# tda2009.net
KiCad netlist of a schematic drawn in EAGLE
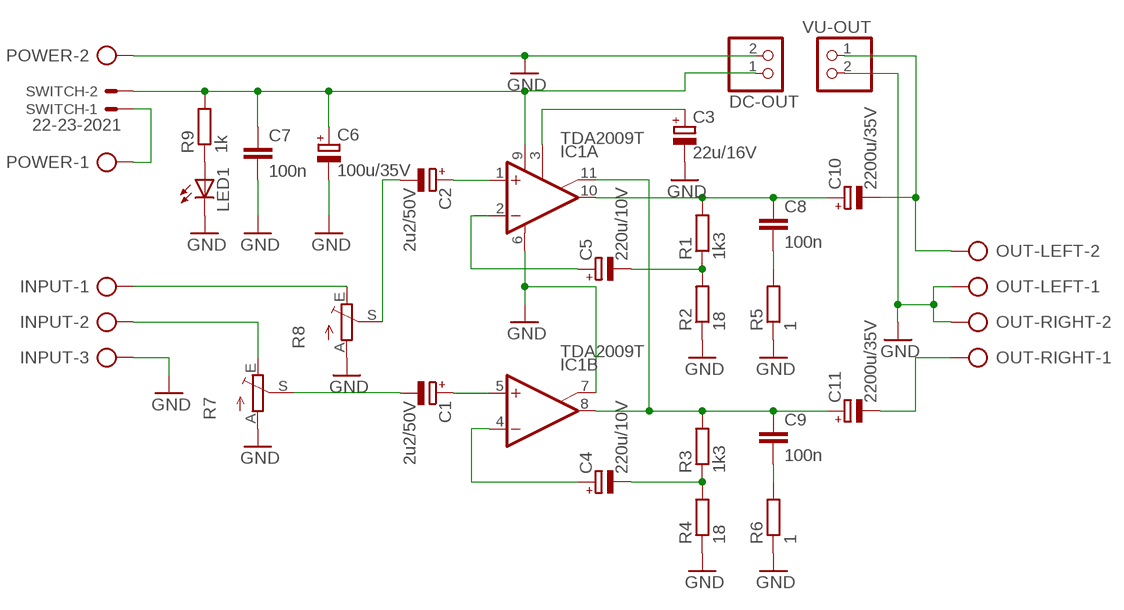
[diagram p0: schematic, sheet 1]

(export (version "E")
  (design (tool "Eeschema 10.0.6"))
  (components
    (comp (ref "C1")
      (value "2u2/50V")
      (footprint "eagle-import:E2,5-5")
      (libsource (lib "eagle-import") (part "CPOL-EUE2.5-5"))
    )
    (comp (ref "C2")
      (value "2u2/50V")
      (footprint "eagle-import:E2,5-5")
      (libsource (lib "eagle-import") (part "CPOL-EUE2.5-5"))
    )
    (comp (ref "C3")
      (value "22u/16V")
      (footprint "eagle-import:E2,5-5")
      (libsource (lib "eagle-import") (part "CPOL-EUE2.5-5"))
    )
    (comp (ref "C4")
      (value "220u/10V")
      (footprint "eagle-import:E2,5-6")
      (libsource (lib "eagle-import") (part "CPOL-EUE2.5-6"))
    )
    (comp (ref "C5")
      (value "220u/10V")
      (footprint "eagle-import:E2,5-6")
      (libsource (lib "eagle-import") (part "CPOL-EUE2.5-6"))
    )
    (comp (ref "C6")
      (value "100u/35V")
      (footprint "eagle-import:E3,5-8")
      (libsource (lib "eagle-import") (part "CPOL-EUE3.5-8"))
    )
    (comp (ref "C7")
      (value "100n")
      (footprint "eagle-import:C025-025X050")
      (libsource (lib "eagle-import") (part "C-EU025-025X050"))
    )
    (comp (ref "C8")
      (value "100n")
      (footprint "eagle-import:C025-025X050")
      (libsource (lib "eagle-import") (part "C-EU025-025X050"))
    )
    (comp (ref "C9")
      (value "100n")
      (footprint "eagle-import:C025-025X050")
      (libsource (lib "eagle-import") (part "C-EU025-025X050"))
    )
    (comp (ref "C10")
      (value "2200u/35V")
      (footprint "eagle-import:E7,5-16")
      (libsource (lib "eagle-import") (part "CPOL-EUE7.5-16"))
    )
    (comp (ref "C11")
      (value "2200u/35V")
      (footprint "eagle-import:E7,5-16")
      (libsource (lib "eagle-import") (part "CPOL-EUE7.5-16"))
    )
    (comp (ref "DC-OUT")
      (value "PINHD-1X2")
      (footprint "eagle-import:1X02")
      (libsource (lib "eagle-import") (part "PINHD-1X2"))
    )
    (comp (ref "IC1")
      (value "TDA2009T")
      (footprint "eagle-import:SIP11")
      (libsource (lib "eagle-import") (part "TDA2009T"))
    )
    (comp (ref "INPUT")
      (value "AK300/3")
      (footprint "eagle-import:AK300_3")
      (libsource (lib "eagle-import") (part "AK300/3"))
    )
    (comp (ref "LED1")
      (value "LED5MM")
      (footprint "eagle-import:LED5MM")
      (libsource (lib "eagle-import") (part "LED5MM"))
    )
    (comp (ref "OUT-LEFT")
      (value "AK300/2")
      (footprint "eagle-import:AK300_2")
      (libsource (lib "eagle-import") (part "AK300/2"))
    )
    (comp (ref "OUT-RIGHT")
      (value "AK300/2")
      (footprint "eagle-import:AK300_2")
      (libsource (lib "eagle-import") (part "AK300/2"))
    )
    (comp (ref "POWER")
      (value "AK300/2")
      (footprint "eagle-import:AK300_2")
      (libsource (lib "eagle-import") (part "AK300/2"))
    )
    (comp (ref "R1")
      (value "1k3")
      (footprint "eagle-import:0207_10")
      (libsource (lib "eagle-import") (part "R-EU_0207/10"))
    )
    (comp (ref "R2")
      (value "18")
      (footprint "eagle-import:0207_10")
      (libsource (lib "eagle-import") (part "R-EU_0207/10"))
    )
    (comp (ref "R3")
      (value "1k3")
      (footprint "eagle-import:0207_10")
      (libsource (lib "eagle-import") (part "R-EU_0207/10"))
    )
    (comp (ref "R4")
      (value "18")
      (footprint "eagle-import:0207_10")
      (libsource (lib "eagle-import") (part "R-EU_0207/10"))
    )
    (comp (ref "R5")
      (value "1")
      (footprint "eagle-import:0207_10")
      (libsource (lib "eagle-import") (part "R-EU_0207/10"))
    )
    (comp (ref "R6")
      (value "1")
      (footprint "eagle-import:0207_10")
      (libsource (lib "eagle-import") (part "R-EU_0207/10"))
    )
    (comp (ref "R7")
      (value "TRIM_EU-RJ9W")
      (footprint "eagle-import:RJ9W")
      (libsource (lib "eagle-import") (part "TRIM_EU-RJ9W"))
    )
    (comp (ref "R8")
      (value "TRIM_EU-RJ9W")
      (footprint "eagle-import:RJ9W")
      (libsource (lib "eagle-import") (part "TRIM_EU-RJ9W"))
    )
    (comp (ref "R9")
      (value "1k")
      (footprint "eagle-import:0207_10")
      (libsource (lib "eagle-import") (part "R-EU_0207/10"))
    )
    (comp (ref "SWITCH")
      (value "22-23-2021")
      (footprint "eagle-import:22-23-2021")
      (libsource (lib "eagle-import") (part "22-23-2021"))
    )
    (comp (ref "VU-OUT")
      (value "PINHD-1X2")
      (footprint "eagle-import:1X02")
      (libsource (lib "eagle-import") (part "PINHD-1X2"))
    )
  )
  (nets
    (net (code "1") (name "GND") (class "Default")
      (node (ref "C3") (pin "-") (pinfunction "-_-") (pintype "passive"))
      (node (ref "C6") (pin "-") (pinfunction "-_-") (pintype "passive"))
      (node (ref "C7") (pin "2") (pinfunction "2_2") (pintype "passive"))
      (node (ref "DC-OUT") (pin "2") (pinfunction "2_2") (pintype "passive"))
      (node (ref "IC1") (pin "6") (pinfunction "GND_6") (pintype "power_in"))
      (node (ref "IC1") (pin "7") (pinfunction "BTSP_7") (pintype "passive"))
      (node (ref "INPUT") (pin "3") (pinfunction "KL_3") (pintype "passive"))
      (node (ref "LED1") (pin "K") (pinfunction "C_K") (pintype "passive"))
      (node (ref "OUT-LEFT") (pin "1") (pinfunction "KL_1") (pintype "passive"))
      (node (ref "OUT-RIGHT") (pin "2") (pinfunction "KL_2") (pintype "passive"))
      (node (ref "POWER") (pin "2") (pinfunction "KL_2") (pintype "passive"))
      (node (ref "R2") (pin "1") (pinfunction "1_1") (pintype "passive"))
      (node (ref "R4") (pin "1") (pinfunction "1_1") (pintype "passive"))
      (node (ref "R5") (pin "1") (pinfunction "1_1") (pintype "passive"))
      (node (ref "R6") (pin "1") (pinfunction "1_1") (pintype "passive"))
      (node (ref "R7") (pin "A") (pinfunction "A_A") (pintype "passive"))
      (node (ref "R8") (pin "A") (pinfunction "A_A") (pintype "passive"))
      (node (ref "VU-OUT") (pin "2") (pinfunction "2_2") (pintype "passive"))
    )
    (net (code "2") (name "Net-(C1-Pad-)") (class "Default")
      (node (ref "C1") (pin "-") (pinfunction "-_-") (pintype "passive"))
      (node (ref "R7") (pin "S") (pinfunction "S_S") (pintype "passive"))
    )
    (net (code "3") (name "Net-(C2-Pad-)") (class "Default")
      (node (ref "C2") (pin "-") (pinfunction "-_-") (pintype "passive"))
      (node (ref "R8") (pin "S") (pinfunction "S_S") (pintype "passive"))
    )
    (net (code "4") (name "Net-(C4-Pad-)") (class "Default")
      (node (ref "C4") (pin "-") (pinfunction "-_-") (pintype "passive"))
      (node (ref "R3") (pin "1") (pinfunction "1_1") (pintype "passive"))
      (node (ref "R4") (pin "2") (pinfunction "2_2") (pintype "passive"))
    )
    (net (code "5") (name "Net-(C5-Pad-)") (class "Default")
      (node (ref "C5") (pin "-") (pinfunction "-_-") (pintype "passive"))
      (node (ref "R1") (pin "1") (pinfunction "1_1") (pintype "passive"))
      (node (ref "R2") (pin "2") (pinfunction "2_2") (pintype "passive"))
    )
    (net (code "6") (name "Net-(C8-Pad2)") (class "Default")
      (node (ref "C8") (pin "2") (pinfunction "2_2") (pintype "passive"))
      (node (ref "R5") (pin "2") (pinfunction "2_2") (pintype "passive"))
    )
    (net (code "7") (name "Net-(C9-Pad2)") (class "Default")
      (node (ref "C9") (pin "2") (pinfunction "2_2") (pintype "passive"))
      (node (ref "R6") (pin "2") (pinfunction "2_2") (pintype "passive"))
    )
    (net (code "8") (name "Net-(IC1A-+IN)") (class "Default")
      (node (ref "C2") (pin "+") (pinfunction "+_+") (pintype "passive"))
      (node (ref "IC1") (pin "1") (pinfunction "+IN_1") (pintype "input"))
    )
    (net (code "9") (name "Net-(IC1A--IN)") (class "Default")
      (node (ref "C5") (pin "+") (pinfunction "+_+") (pintype "passive"))
      (node (ref "IC1") (pin "2") (pinfunction "-IN_2") (pintype "input"))
    )
    (net (code "10") (name "Net-(IC1A-BTSP)") (class "Default")
      (node (ref "C11") (pin "+") (pinfunction "+_+") (pintype "passive"))
      (node (ref "C9") (pin "1") (pinfunction "1_1") (pintype "passive"))
      (node (ref "IC1") (pin "11") (pinfunction "BTSP_11") (pintype "passive"))
      (node (ref "IC1") (pin "8") (pinfunction "OUT_8") (pintype "output"))
      (node (ref "R3") (pin "2") (pinfunction "2_2") (pintype "passive"))
    )
    (net (code "11") (name "Net-(IC1A-OUT)") (class "Default")
      (node (ref "C10") (pin "+") (pinfunction "+_+") (pintype "passive"))
      (node (ref "C8") (pin "1") (pinfunction "1_1") (pintype "passive"))
      (node (ref "IC1") (pin "10") (pinfunction "OUT_10") (pintype "output"))
      (node (ref "R1") (pin "2") (pinfunction "2_2") (pintype "passive"))
    )
    (net (code "12") (name "Net-(IC1A-SVRR)") (class "Default")
      (node (ref "C3") (pin "+") (pinfunction "+_+") (pintype "passive"))
      (node (ref "IC1") (pin "3") (pinfunction "SVRR_3") (pintype "passive"))
    )
    (net (code "13") (name "Net-(IC1A-V+)") (class "Default")
      (node (ref "C6") (pin "+") (pinfunction "+_+") (pintype "passive"))
      (node (ref "C7") (pin "1") (pinfunction "1_1") (pintype "passive"))
      (node (ref "DC-OUT") (pin "1") (pinfunction "1_1") (pintype "passive"))
      (node (ref "IC1") (pin "9") (pinfunction "V+_9") (pintype "power_in"))
      (node (ref "R9") (pin "2") (pinfunction "2_2") (pintype "passive"))
      (node (ref "SWITCH") (pin "2") (pinfunction "S_2") (pintype "passive"))
    )
    (net (code "14") (name "Net-(IC1B-+IN)") (class "Default")
      (node (ref "C1") (pin "+") (pinfunction "+_+") (pintype "passive"))
      (node (ref "IC1") (pin "5") (pinfunction "+IN_5") (pintype "input"))
    )
    (net (code "15") (name "Net-(IC1B--IN)") (class "Default")
      (node (ref "C4") (pin "+") (pinfunction "+_+") (pintype "passive"))
      (node (ref "IC1") (pin "4") (pinfunction "-IN_4") (pintype "input"))
    )
    (net (code "16") (name "Net-(INPUTA-KL)") (class "Default")
      (node (ref "INPUT") (pin "1") (pinfunction "KL_1") (pintype "passive"))
      (node (ref "R8") (pin "E") (pinfunction "E_E") (pintype "passive"))
    )
    (net (code "17") (name "Net-(INPUTB-KL)") (class "Default")
      (node (ref "INPUT") (pin "2") (pinfunction "KL_2") (pintype "passive"))
      (node (ref "R7") (pin "E") (pinfunction "E_E") (pintype "passive"))
    )
    (net (code "18") (name "Net-(LED1-PadA)") (class "Default")
      (node (ref "LED1") (pin "A") (pinfunction "A_A") (pintype "passive"))
      (node (ref "R9") (pin "1") (pinfunction "1_1") (pintype "passive"))
    )
    (net (code "19") (name "Net-(OUT-LEFTB-KL)") (class "Default")
      (node (ref "C10") (pin "-") (pinfunction "-_-") (pintype "passive"))
      (node (ref "OUT-LEFT") (pin "2") (pinfunction "KL_2") (pintype "passive"))
      (node (ref "VU-OUT") (pin "1") (pinfunction "1_1") (pintype "passive"))
    )
    (net (code "20") (name "Net-(OUT-RIGHTA-KL)") (class "Default")
      (node (ref "C11") (pin "-") (pinfunction "-_-") (pintype "passive"))
      (node (ref "OUT-RIGHT") (pin "1") (pinfunction "KL_1") (pintype "passive"))
    )
    (net (code "21") (name "Net-(POWERA-KL)") (class "Default")
      (node (ref "POWER") (pin "1") (pinfunction "KL_1") (pintype "passive"))
      (node (ref "SWITCH") (pin "1") (pinfunction "S_1") (pintype "passive"))
    )
  )
)
